# 21_GPIOs_EXP.net
KiCad netlist of a schematic drawn in Altium Designer
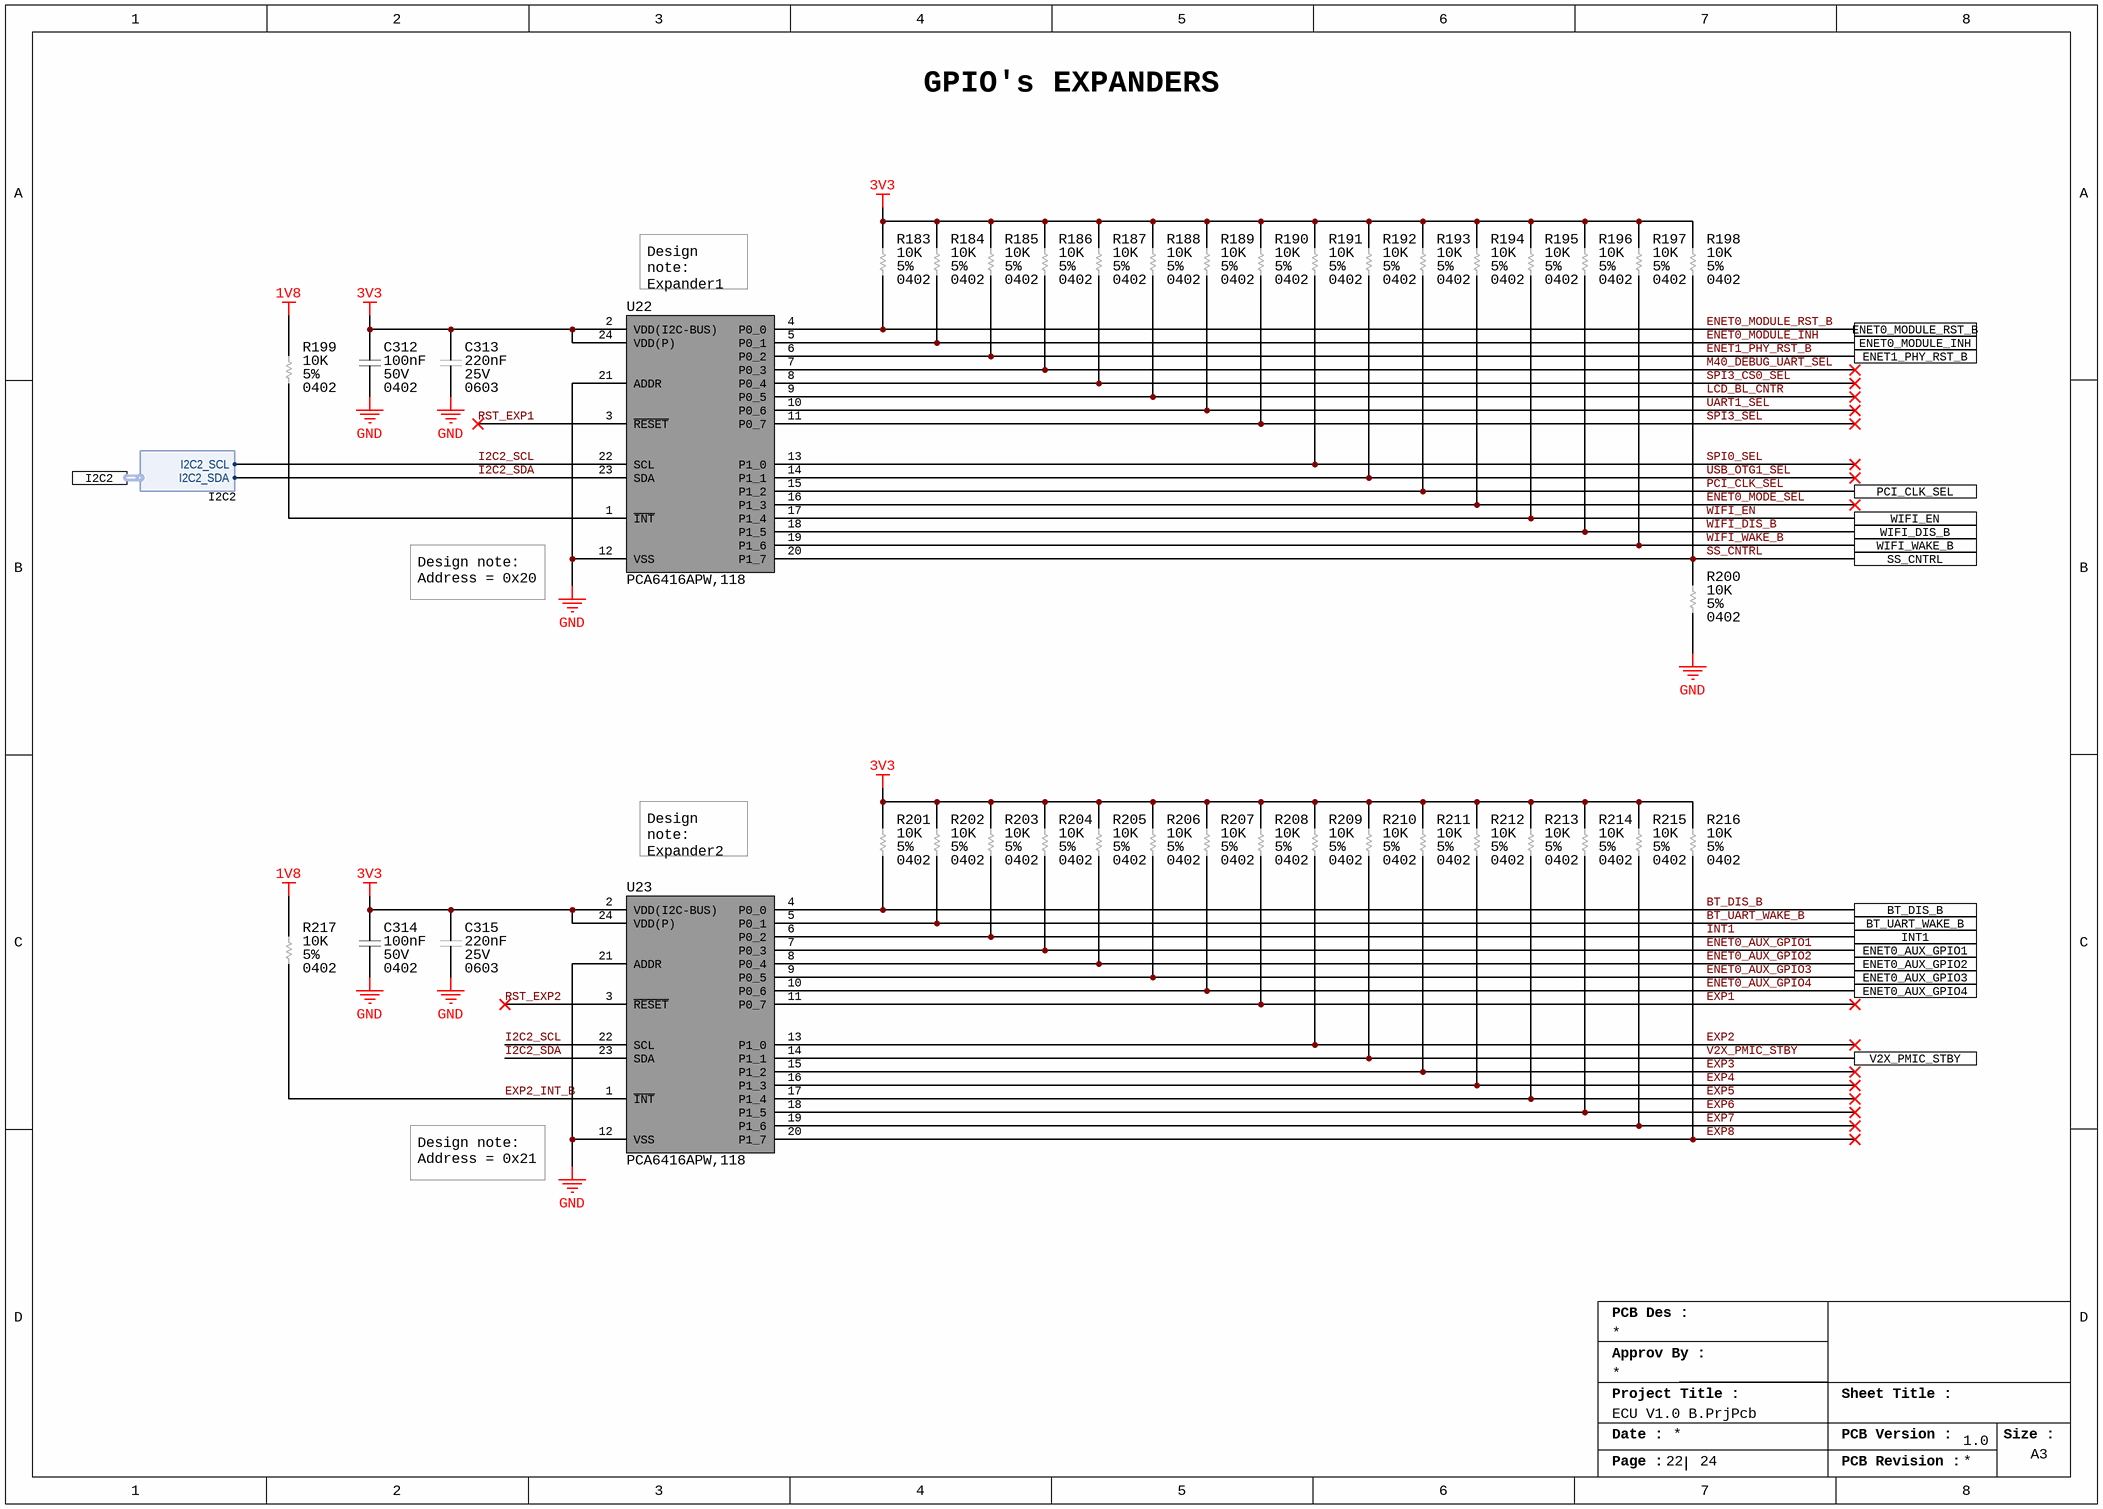
[diagram p0: 21_GPIOs_EXP.SchDoc]

(export (version "E")
  (design (tool "Eeschema 10.0.6"))
  (components
    (comp (ref "C312")
      (value "GRM155R71H104KE14D")
      (footprint "CAP_0402_CAPC1005X05N")
      (description "Multilayer Ceramic Capacitor, 0.1 uF, 16 V, ± 10%, X7R, 0402 [1005 Metric]")
      (fields
        (field (name "MANUFACTURER") "Murata")
        (field (name "TOLERANCE") "10%")
        (field (name "VOLTAGE RATING") "50V")
        (field (name "CAPACITANCE") "100nF")
        (field (name "CASE/PACKAGE") "0402")
      )
      (libsource (lib "Electronic Devices_LIB") (part "CAP_100NF_50V_X7R_0402"))
    )
    (comp (ref "C313")
      (value "GRM188R71E224KA88D")
      (footprint "CAP_0603_CAPC1608X08N")
      (description "Multilayer Ceramic Capacitor, 0.22 uF, 25 V, ± 10%, X7R, 0603 [1608 Metric]")
      (fields
        (field (name "MANUFACTURER") "Murata")
        (field (name "TOLERANCE") "10%")
        (field (name "CASE/PACKAGE") "0603")
        (field (name "VOLTAGE RATING") "25V")
        (field (name "CAPACITANCE") "220nF")
      )
      (libsource (lib "Electronic Devices_LIB") (part "CAP_0.22uF_25V_X7R_0603"))
    )
    (comp (ref "C314")
      (value "GRM155R71H104KE14D")
      (footprint "CAP_0402_CAPC1005X05N")
      (description "Multilayer Ceramic Capacitor, 0.1 uF, 16 V, ± 10%, X7R, 0402 [1005 Metric]")
      (fields
        (field (name "MANUFACTURER") "Murata")
        (field (name "TOLERANCE") "10%")
        (field (name "VOLTAGE RATING") "50V")
        (field (name "CAPACITANCE") "100nF")
        (field (name "CASE/PACKAGE") "0402")
      )
      (libsource (lib "Electronic Devices_LIB") (part "CAP_100NF_50V_X7R_0402"))
    )
    (comp (ref "C315")
      (value "GRM188R71E224KA88D")
      (footprint "CAP_0603_CAPC1608X08N")
      (description "Multilayer Ceramic Capacitor, 0.22 uF, 25 V, ± 10%, X7R, 0603 [1608 Metric]")
      (fields
        (field (name "MANUFACTURER") "Murata")
        (field (name "TOLERANCE") "10%")
        (field (name "CASE/PACKAGE") "0603")
        (field (name "VOLTAGE RATING") "25V")
        (field (name "CAPACITANCE") "220nF")
      )
      (libsource (lib "Electronic Devices_LIB") (part "CAP_0.22uF_25V_X7R_0603"))
    )
    (comp (ref "R183")
      (value "ERJ-2GEJ103X")
      (footprint "RES_0402_RESC1005X04N")
      (description "Res Thick Film 0402 10K Ohm 5% 1/10W ±200ppm/°C Molded SMD Punched Carrier T/R")
      (fields
        (field (name "MANUFACTURER") "Panasonic")
        (field (name "TOLERANCE") "5%")
        (field (name "RESISTANCE") "10K")
        (field (name "CASE/PACKAGE") "0402")
      )
      (libsource (lib "Electronic Devices_LIB") (part "RES_10K_5%_100mW_0402"))
    )
    (comp (ref "R184")
      (value "ERJ-2GEJ103X")
      (footprint "RES_0402_RESC1005X04N")
      (description "Res Thick Film 0402 10K Ohm 5% 1/10W ±200ppm/°C Molded SMD Punched Carrier T/R")
      (fields
        (field (name "MANUFACTURER") "Panasonic")
        (field (name "TOLERANCE") "5%")
        (field (name "RESISTANCE") "10K")
        (field (name "CASE/PACKAGE") "0402")
      )
      (libsource (lib "Electronic Devices_LIB") (part "RES_10K_5%_100mW_0402"))
    )
    (comp (ref "R185")
      (value "ERJ-2GEJ103X")
      (footprint "RES_0402_RESC1005X04N")
      (description "Res Thick Film 0402 10K Ohm 5% 1/10W ±200ppm/°C Molded SMD Punched Carrier T/R")
      (fields
        (field (name "MANUFACTURER") "Panasonic")
        (field (name "TOLERANCE") "5%")
        (field (name "RESISTANCE") "10K")
        (field (name "CASE/PACKAGE") "0402")
      )
      (libsource (lib "Electronic Devices_LIB") (part "RES_10K_5%_100mW_0402"))
    )
    (comp (ref "R186")
      (value "ERJ-2GEJ103X")
      (footprint "RES_0402_RESC1005X04N")
      (description "Res Thick Film 0402 10K Ohm 5% 1/10W ±200ppm/°C Molded SMD Punched Carrier T/R")
      (fields
        (field (name "MANUFACTURER") "Panasonic")
        (field (name "TOLERANCE") "5%")
        (field (name "RESISTANCE") "10K")
        (field (name "CASE/PACKAGE") "0402")
      )
      (libsource (lib "Electronic Devices_LIB") (part "RES_10K_5%_100mW_0402"))
    )
    (comp (ref "R187")
      (value "ERJ-2GEJ103X")
      (footprint "RES_0402_RESC1005X04N")
      (description "Res Thick Film 0402 10K Ohm 5% 1/10W ±200ppm/°C Molded SMD Punched Carrier T/R")
      (fields
        (field (name "MANUFACTURER") "Panasonic")
        (field (name "TOLERANCE") "5%")
        (field (name "RESISTANCE") "10K")
        (field (name "CASE/PACKAGE") "0402")
      )
      (libsource (lib "Electronic Devices_LIB") (part "RES_10K_5%_100mW_0402"))
    )
    (comp (ref "R188")
      (value "ERJ-2GEJ103X")
      (footprint "RES_0402_RESC1005X04N")
      (description "Res Thick Film 0402 10K Ohm 5% 1/10W ±200ppm/°C Molded SMD Punched Carrier T/R")
      (fields
        (field (name "MANUFACTURER") "Panasonic")
        (field (name "TOLERANCE") "5%")
        (field (name "RESISTANCE") "10K")
        (field (name "CASE/PACKAGE") "0402")
      )
      (libsource (lib "Electronic Devices_LIB") (part "RES_10K_5%_100mW_0402"))
    )
    (comp (ref "R189")
      (value "ERJ-2GEJ103X")
      (footprint "RES_0402_RESC1005X04N")
      (description "Res Thick Film 0402 10K Ohm 5% 1/10W ±200ppm/°C Molded SMD Punched Carrier T/R")
      (fields
        (field (name "MANUFACTURER") "Panasonic")
        (field (name "TOLERANCE") "5%")
        (field (name "RESISTANCE") "10K")
        (field (name "CASE/PACKAGE") "0402")
      )
      (libsource (lib "Electronic Devices_LIB") (part "RES_10K_5%_100mW_0402"))
    )
    (comp (ref "R190")
      (value "ERJ-2GEJ103X")
      (footprint "RES_0402_RESC1005X04N")
      (description "Res Thick Film 0402 10K Ohm 5% 1/10W ±200ppm/°C Molded SMD Punched Carrier T/R")
      (fields
        (field (name "MANUFACTURER") "Panasonic")
        (field (name "TOLERANCE") "5%")
        (field (name "RESISTANCE") "10K")
        (field (name "CASE/PACKAGE") "0402")
      )
      (libsource (lib "Electronic Devices_LIB") (part "RES_10K_5%_100mW_0402"))
    )
    (comp (ref "R191")
      (value "ERJ-2GEJ103X")
      (footprint "RES_0402_RESC1005X04N")
      (description "Res Thick Film 0402 10K Ohm 5% 1/10W ±200ppm/°C Molded SMD Punched Carrier T/R")
      (fields
        (field (name "MANUFACTURER") "Panasonic")
        (field (name "TOLERANCE") "5%")
        (field (name "RESISTANCE") "10K")
        (field (name "CASE/PACKAGE") "0402")
      )
      (libsource (lib "Electronic Devices_LIB") (part "RES_10K_5%_100mW_0402"))
    )
    (comp (ref "R192")
      (value "ERJ-2GEJ103X")
      (footprint "RES_0402_RESC1005X04N")
      (description "Res Thick Film 0402 10K Ohm 5% 1/10W ±200ppm/°C Molded SMD Punched Carrier T/R")
      (fields
        (field (name "MANUFACTURER") "Panasonic")
        (field (name "TOLERANCE") "5%")
        (field (name "RESISTANCE") "10K")
        (field (name "CASE/PACKAGE") "0402")
      )
      (libsource (lib "Electronic Devices_LIB") (part "RES_10K_5%_100mW_0402"))
    )
    (comp (ref "R193")
      (value "ERJ-2GEJ103X")
      (footprint "RES_0402_RESC1005X04N")
      (description "Res Thick Film 0402 10K Ohm 5% 1/10W ±200ppm/°C Molded SMD Punched Carrier T/R")
      (fields
        (field (name "MANUFACTURER") "Panasonic")
        (field (name "TOLERANCE") "5%")
        (field (name "RESISTANCE") "10K")
        (field (name "CASE/PACKAGE") "0402")
      )
      (libsource (lib "Electronic Devices_LIB") (part "RES_10K_5%_100mW_0402"))
    )
    (comp (ref "R194")
      (value "ERJ-2GEJ103X")
      (footprint "RES_0402_RESC1005X04N")
      (description "Res Thick Film 0402 10K Ohm 5% 1/10W ±200ppm/°C Molded SMD Punched Carrier T/R")
      (fields
        (field (name "MANUFACTURER") "Panasonic")
        (field (name "TOLERANCE") "5%")
        (field (name "RESISTANCE") "10K")
        (field (name "CASE/PACKAGE") "0402")
      )
      (libsource (lib "Electronic Devices_LIB") (part "RES_10K_5%_100mW_0402"))
    )
    (comp (ref "R195")
      (value "ERJ-2GEJ103X")
      (footprint "RES_0402_RESC1005X04N")
      (description "Res Thick Film 0402 10K Ohm 5% 1/10W ±200ppm/°C Molded SMD Punched Carrier T/R")
      (fields
        (field (name "MANUFACTURER") "Panasonic")
        (field (name "TOLERANCE") "5%")
        (field (name "RESISTANCE") "10K")
        (field (name "CASE/PACKAGE") "0402")
      )
      (libsource (lib "Electronic Devices_LIB") (part "RES_10K_5%_100mW_0402"))
    )
    (comp (ref "R196")
      (value "ERJ-2GEJ103X")
      (footprint "RES_0402_RESC1005X04N")
      (description "Res Thick Film 0402 10K Ohm 5% 1/10W ±200ppm/°C Molded SMD Punched Carrier T/R")
      (fields
        (field (name "MANUFACTURER") "Panasonic")
        (field (name "TOLERANCE") "5%")
        (field (name "RESISTANCE") "10K")
        (field (name "CASE/PACKAGE") "0402")
      )
      (libsource (lib "Electronic Devices_LIB") (part "RES_10K_5%_100mW_0402"))
    )
    (comp (ref "R197")
      (value "ERJ-2GEJ103X")
      (footprint "RES_0402_RESC1005X04N")
      (description "Res Thick Film 0402 10K Ohm 5% 1/10W ±200ppm/°C Molded SMD Punched Carrier T/R")
      (fields
        (field (name "MANUFACTURER") "Panasonic")
        (field (name "TOLERANCE") "5%")
        (field (name "RESISTANCE") "10K")
        (field (name "CASE/PACKAGE") "0402")
      )
      (libsource (lib "Electronic Devices_LIB") (part "RES_10K_5%_100mW_0402"))
    )
    (comp (ref "R198")
      (value "ERJ-2GEJ103X")
      (footprint "RES_0402_RESC1005X04N")
      (description "Res Thick Film 0402 10K Ohm 5% 1/10W ±200ppm/°C Molded SMD Punched Carrier T/R")
      (fields
        (field (name "MANUFACTURER") "Panasonic")
        (field (name "TOLERANCE") "5%")
        (field (name "RESISTANCE") "10K")
        (field (name "CASE/PACKAGE") "0402")
      )
      (libsource (lib "Electronic Devices_LIB") (part "RES_10K_5%_100mW_0402"))
    )
    (comp (ref "R199")
      (value "ERJ-2GEJ103X")
      (footprint "RES_0402_RESC1005X04N")
      (description "Res Thick Film 0402 10K Ohm 5% 1/10W ±200ppm/°C Molded SMD Punched Carrier T/R")
      (fields
        (field (name "MANUFACTURER") "Panasonic")
        (field (name "TOLERANCE") "5%")
        (field (name "RESISTANCE") "10K")
        (field (name "CASE/PACKAGE") "0402")
      )
      (libsource (lib "Electronic Devices_LIB") (part "RES_10K_5%_100mW_0402"))
    )
    (comp (ref "R200")
      (value "ERJ-2GEJ103X")
      (footprint "RES_0402_RESC1005X04N")
      (description "Res Thick Film 0402 10K Ohm 5% 1/10W ±200ppm/°C Molded SMD Punched Carrier T/R")
      (fields
        (field (name "MANUFACTURER") "Panasonic")
        (field (name "TOLERANCE") "5%")
        (field (name "RESISTANCE") "10K")
        (field (name "CASE/PACKAGE") "0402")
      )
      (libsource (lib "Electronic Devices_LIB") (part "RES_10K_5%_100mW_0402"))
    )
    (comp (ref "R201")
      (value "ERJ-2GEJ103X")
      (footprint "RES_0402_RESC1005X04N")
      (description "Res Thick Film 0402 10K Ohm 5% 1/10W ±200ppm/°C Molded SMD Punched Carrier T/R")
      (fields
        (field (name "MANUFACTURER") "Panasonic")
        (field (name "TOLERANCE") "5%")
        (field (name "RESISTANCE") "10K")
        (field (name "CASE/PACKAGE") "0402")
      )
      (libsource (lib "Electronic Devices_LIB") (part "RES_10K_5%_100mW_0402"))
    )
    (comp (ref "R202")
      (value "ERJ-2GEJ103X")
      (footprint "RES_0402_RESC1005X04N")
      (description "Res Thick Film 0402 10K Ohm 5% 1/10W ±200ppm/°C Molded SMD Punched Carrier T/R")
      (fields
        (field (name "MANUFACTURER") "Panasonic")
        (field (name "TOLERANCE") "5%")
        (field (name "RESISTANCE") "10K")
        (field (name "CASE/PACKAGE") "0402")
      )
      (libsource (lib "Electronic Devices_LIB") (part "RES_10K_5%_100mW_0402"))
    )
    (comp (ref "R203")
      (value "ERJ-2GEJ103X")
      (footprint "RES_0402_RESC1005X04N")
      (description "Res Thick Film 0402 10K Ohm 5% 1/10W ±200ppm/°C Molded SMD Punched Carrier T/R")
      (fields
        (field (name "MANUFACTURER") "Panasonic")
        (field (name "TOLERANCE") "5%")
        (field (name "RESISTANCE") "10K")
        (field (name "CASE/PACKAGE") "0402")
      )
      (libsource (lib "Electronic Devices_LIB") (part "RES_10K_5%_100mW_0402"))
    )
    (comp (ref "R204")
      (value "ERJ-2GEJ103X")
      (footprint "RES_0402_RESC1005X04N")
      (description "Res Thick Film 0402 10K Ohm 5% 1/10W ±200ppm/°C Molded SMD Punched Carrier T/R")
      (fields
        (field (name "MANUFACTURER") "Panasonic")
        (field (name "TOLERANCE") "5%")
        (field (name "RESISTANCE") "10K")
        (field (name "CASE/PACKAGE") "0402")
      )
      (libsource (lib "Electronic Devices_LIB") (part "RES_10K_5%_100mW_0402"))
    )
    (comp (ref "R205")
      (value "ERJ-2GEJ103X")
      (footprint "RES_0402_RESC1005X04N")
      (description "Res Thick Film 0402 10K Ohm 5% 1/10W ±200ppm/°C Molded SMD Punched Carrier T/R")
      (fields
        (field (name "MANUFACTURER") "Panasonic")
        (field (name "TOLERANCE") "5%")
        (field (name "RESISTANCE") "10K")
        (field (name "CASE/PACKAGE") "0402")
      )
      (libsource (lib "Electronic Devices_LIB") (part "RES_10K_5%_100mW_0402"))
    )
    (comp (ref "R206")
      (value "ERJ-2GEJ103X")
      (footprint "RES_0402_RESC1005X04N")
      (description "Res Thick Film 0402 10K Ohm 5% 1/10W ±200ppm/°C Molded SMD Punched Carrier T/R")
      (fields
        (field (name "MANUFACTURER") "Panasonic")
        (field (name "TOLERANCE") "5%")
        (field (name "RESISTANCE") "10K")
        (field (name "CASE/PACKAGE") "0402")
      )
      (libsource (lib "Electronic Devices_LIB") (part "RES_10K_5%_100mW_0402"))
    )
    (comp (ref "R207")
      (value "ERJ-2GEJ103X")
      (footprint "RES_0402_RESC1005X04N")
      (description "Res Thick Film 0402 10K Ohm 5% 1/10W ±200ppm/°C Molded SMD Punched Carrier T/R")
      (fields
        (field (name "MANUFACTURER") "Panasonic")
        (field (name "TOLERANCE") "5%")
        (field (name "RESISTANCE") "10K")
        (field (name "CASE/PACKAGE") "0402")
      )
      (libsource (lib "Electronic Devices_LIB") (part "RES_10K_5%_100mW_0402"))
    )
    (comp (ref "R208")
      (value "ERJ-2GEJ103X")
      (footprint "RES_0402_RESC1005X04N")
      (description "Res Thick Film 0402 10K Ohm 5% 1/10W ±200ppm/°C Molded SMD Punched Carrier T/R")
      (fields
        (field (name "MANUFACTURER") "Panasonic")
        (field (name "TOLERANCE") "5%")
        (field (name "RESISTANCE") "10K")
        (field (name "CASE/PACKAGE") "0402")
      )
      (libsource (lib "Electronic Devices_LIB") (part "RES_10K_5%_100mW_0402"))
    )
    (comp (ref "R209")
      (value "ERJ-2GEJ103X")
      (footprint "RES_0402_RESC1005X04N")
      (description "Res Thick Film 0402 10K Ohm 5% 1/10W ±200ppm/°C Molded SMD Punched Carrier T/R")
      (fields
        (field (name "MANUFACTURER") "Panasonic")
        (field (name "TOLERANCE") "5%")
        (field (name "RESISTANCE") "10K")
        (field (name "CASE/PACKAGE") "0402")
      )
      (libsource (lib "Electronic Devices_LIB") (part "RES_10K_5%_100mW_0402"))
    )
    (comp (ref "R210")
      (value "ERJ-2GEJ103X")
      (footprint "RES_0402_RESC1005X04N")
      (description "Res Thick Film 0402 10K Ohm 5% 1/10W ±200ppm/°C Molded SMD Punched Carrier T/R")
      (fields
        (field (name "MANUFACTURER") "Panasonic")
        (field (name "TOLERANCE") "5%")
        (field (name "RESISTANCE") "10K")
        (field (name "CASE/PACKAGE") "0402")
      )
      (libsource (lib "Electronic Devices_LIB") (part "RES_10K_5%_100mW_0402"))
    )
    (comp (ref "R211")
      (value "ERJ-2GEJ103X")
      (footprint "RES_0402_RESC1005X04N")
      (description "Res Thick Film 0402 10K Ohm 5% 1/10W ±200ppm/°C Molded SMD Punched Carrier T/R")
      (fields
        (field (name "MANUFACTURER") "Panasonic")
        (field (name "TOLERANCE") "5%")
        (field (name "RESISTANCE") "10K")
        (field (name "CASE/PACKAGE") "0402")
      )
      (libsource (lib "Electronic Devices_LIB") (part "RES_10K_5%_100mW_0402"))
    )
    (comp (ref "R212")
      (value "ERJ-2GEJ103X")
      (footprint "RES_0402_RESC1005X04N")
      (description "Res Thick Film 0402 10K Ohm 5% 1/10W ±200ppm/°C Molded SMD Punched Carrier T/R")
      (fields
        (field (name "MANUFACTURER") "Panasonic")
        (field (name "TOLERANCE") "5%")
        (field (name "RESISTANCE") "10K")
        (field (name "CASE/PACKAGE") "0402")
      )
      (libsource (lib "Electronic Devices_LIB") (part "RES_10K_5%_100mW_0402"))
    )
    (comp (ref "R213")
      (value "ERJ-2GEJ103X")
      (footprint "RES_0402_RESC1005X04N")
      (description "Res Thick Film 0402 10K Ohm 5% 1/10W ±200ppm/°C Molded SMD Punched Carrier T/R")
      (fields
        (field (name "MANUFACTURER") "Panasonic")
        (field (name "TOLERANCE") "5%")
        (field (name "RESISTANCE") "10K")
        (field (name "CASE/PACKAGE") "0402")
      )
      (libsource (lib "Electronic Devices_LIB") (part "RES_10K_5%_100mW_0402"))
    )
    (comp (ref "R214")
      (value "ERJ-2GEJ103X")
      (footprint "RES_0402_RESC1005X04N")
      (description "Res Thick Film 0402 10K Ohm 5% 1/10W ±200ppm/°C Molded SMD Punched Carrier T/R")
      (fields
        (field (name "MANUFACTURER") "Panasonic")
        (field (name "TOLERANCE") "5%")
        (field (name "RESISTANCE") "10K")
        (field (name "CASE/PACKAGE") "0402")
      )
      (libsource (lib "Electronic Devices_LIB") (part "RES_10K_5%_100mW_0402"))
    )
    (comp (ref "R215")
      (value "ERJ-2GEJ103X")
      (footprint "RES_0402_RESC1005X04N")
      (description "Res Thick Film 0402 10K Ohm 5% 1/10W ±200ppm/°C Molded SMD Punched Carrier T/R")
      (fields
        (field (name "MANUFACTURER") "Panasonic")
        (field (name "TOLERANCE") "5%")
        (field (name "RESISTANCE") "10K")
        (field (name "CASE/PACKAGE") "0402")
      )
      (libsource (lib "Electronic Devices_LIB") (part "RES_10K_5%_100mW_0402"))
    )
    (comp (ref "R216")
      (value "ERJ-2GEJ103X")
      (footprint "RES_0402_RESC1005X04N")
      (description "Res Thick Film 0402 10K Ohm 5% 1/10W ±200ppm/°C Molded SMD Punched Carrier T/R")
      (fields
        (field (name "MANUFACTURER") "Panasonic")
        (field (name "TOLERANCE") "5%")
        (field (name "RESISTANCE") "10K")
        (field (name "CASE/PACKAGE") "0402")
      )
      (libsource (lib "Electronic Devices_LIB") (part "RES_10K_5%_100mW_0402"))
    )
    (comp (ref "R217")
      (value "ERJ-2GEJ103X")
      (footprint "RES_0402_RESC1005X04N")
      (description "Res Thick Film 0402 10K Ohm 5% 1/10W ±200ppm/°C Molded SMD Punched Carrier T/R")
      (fields
        (field (name "MANUFACTURER") "Panasonic")
        (field (name "TOLERANCE") "5%")
        (field (name "RESISTANCE") "10K")
        (field (name "CASE/PACKAGE") "0402")
      )
      (libsource (lib "Electronic Devices_LIB") (part "RES_10K_5%_100mW_0402"))
    )
    (comp (ref "U22")
      (value "PCA6416APW,118")
      (footprint "PCA6416APW118")
      (description "I2C/SMBus Interface 100kHz/400kHz 5.5V 24-Pin TSSOP T/R")
      (fields (field (name "MANUFACTURER") "NXP Semiconductors"))
      (libsource (lib "Electronic Devices_LIB") (part "IC_EXPANDER_16_PCA6416APW,118"))
    )
    (comp (ref "U23")
      (value "PCA6416APW,118")
      (footprint "PCA6416APW118")
      (description "I2C/SMBus Interface 100kHz/400kHz 5.5V 24-Pin TSSOP T/R")
      (fields (field (name "MANUFACTURER") "NXP Semiconductors"))
      (libsource (lib "Electronic Devices_LIB") (part "IC_EXPANDER_16_PCA6416APW,118"))
    )
  )
  (nets
    (net (code "2") (name "/BT_DIS_B") (class "Default")
      (node (ref "R201") (pin "1") (pinfunction "1_1") (pintype "passive"))
      (node (ref "U23") (pin "4") (pinfunction "P0_0_4") (pintype "passive"))
    )
    (net (code "3") (name "/BT_UART_WAKE_B") (class "Default")
      (node (ref "R202") (pin "1") (pinfunction "1_1") (pintype "passive"))
      (node (ref "U23") (pin "5") (pinfunction "P0_1_5") (pintype "passive"))
    )
    (net (code "4") (name "/ENET0_AUX_GPIO1") (class "Default")
      (node (ref "R204") (pin "1") (pinfunction "1_1") (pintype "passive"))
      (node (ref "U23") (pin "7") (pinfunction "P0_3_7") (pintype "passive"))
    )
    (net (code "5") (name "/ENET0_AUX_GPIO2") (class "Default")
      (node (ref "R205") (pin "1") (pinfunction "1_1") (pintype "passive"))
      (node (ref "U23") (pin "8") (pinfunction "P0_4_8") (pintype "passive"))
    )
    (net (code "6") (name "/ENET0_AUX_GPIO3") (class "Default")
      (node (ref "R206") (pin "1") (pinfunction "1_1") (pintype "passive"))
      (node (ref "U23") (pin "9") (pinfunction "P0_5_9") (pintype "passive"))
    )
    (net (code "7") (name "/ENET0_AUX_GPIO4") (class "Default")
      (node (ref "R207") (pin "1") (pinfunction "1_1") (pintype "passive"))
      (node (ref "U23") (pin "10") (pinfunction "P0_6_10") (pintype "passive"))
    )
    (net (code "8") (name "/ENET0_MODE_SEL") (class "Default")
      (node (ref "R194") (pin "1") (pinfunction "1_1") (pintype "passive"))
      (node (ref "U22") (pin "16") (pinfunction "P1_3_16") (pintype "passive"))
    )
    (net (code "9") (name "/ENET0_MODULE_INH") (class "Default")
      (node (ref "R184") (pin "1") (pinfunction "1_1") (pintype "passive"))
      (node (ref "U22") (pin "5") (pinfunction "P0_1_5") (pintype "passive"))
    )
    (net (code "10") (name "/ENET0_MODULE_RST_B") (class "Default")
      (node (ref "R183") (pin "1") (pinfunction "1_1") (pintype "passive"))
      (node (ref "U22") (pin "4") (pinfunction "P0_0_4") (pintype "passive"))
    )
    (net (code "11") (name "/ENET1_PHY_RST_B") (class "Default")
      (node (ref "R185") (pin "1") (pinfunction "1_1") (pintype "passive"))
      (node (ref "U22") (pin "6") (pinfunction "P0_2_6") (pintype "passive"))
    )
    (net (code "12") (name "/EXP1") (class "Default")
      (node (ref "R208") (pin "1") (pinfunction "1_1") (pintype "passive"))
      (node (ref "U23") (pin "11") (pinfunction "P0_7_11") (pintype "passive"))
    )
    (net (code "13") (name "/EXP2") (class "Default")
      (node (ref "R209") (pin "1") (pinfunction "1_1") (pintype "passive"))
      (node (ref "U23") (pin "13") (pinfunction "P1_0_13") (pintype "passive"))
    )
    (net (code "14") (name "/EXP2_INT_B") (class "Default")
      (node (ref "R217") (pin "1") (pinfunction "1_1") (pintype "passive"))
      (node (ref "U23") (pin "1") (pinfunction "~{INT}_1") (pintype "passive"))
    )
    (net (code "15") (name "/EXP3") (class "Default")
      (node (ref "R211") (pin "1") (pinfunction "1_1") (pintype "passive"))
      (node (ref "U23") (pin "15") (pinfunction "P1_2_15") (pintype "passive"))
    )
    (net (code "16") (name "/EXP4") (class "Default")
      (node (ref "R212") (pin "1") (pinfunction "1_1") (pintype "passive"))
      (node (ref "U23") (pin "16") (pinfunction "P1_3_16") (pintype "passive"))
    )
    (net (code "17") (name "/EXP5") (class "Default")
      (node (ref "R213") (pin "1") (pinfunction "1_1") (pintype "passive"))
      (node (ref "U23") (pin "17") (pinfunction "P1_4_17") (pintype "passive"))
    )
    (net (code "18") (name "/EXP6") (class "Default")
      (node (ref "R214") (pin "1") (pinfunction "1_1") (pintype "passive"))
      (node (ref "U23") (pin "18") (pinfunction "P1_5_18") (pintype "passive"))
    )
    (net (code "19") (name "/EXP7") (class "Default")
      (node (ref "R215") (pin "1") (pinfunction "1_1") (pintype "passive"))
      (node (ref "U23") (pin "19") (pinfunction "P1_6_19") (pintype "passive"))
    )
    (net (code "20") (name "/EXP8") (class "Default")
      (node (ref "R216") (pin "1") (pinfunction "1_1") (pintype "passive"))
      (node (ref "U23") (pin "20") (pinfunction "P1_7_20") (pintype "passive"))
    )
    (net (code "21") (name "/I2C2_SCL") (class "Default")
      (node (ref "U22") (pin "22") (pinfunction "SCL_22") (pintype "passive"))
      (node (ref "U23") (pin "22") (pinfunction "SCL_22") (pintype "passive"))
    )
    (net (code "22") (name "/I2C2_SDA") (class "Default")
      (node (ref "U22") (pin "23") (pinfunction "SDA_23") (pintype "passive"))
      (node (ref "U23") (pin "23") (pinfunction "SDA_23") (pintype "passive"))
    )
    (net (code "23") (name "/INT1") (class "Default")
      (node (ref "R203") (pin "1") (pinfunction "1_1") (pintype "passive"))
      (node (ref "U23") (pin "6") (pinfunction "P0_2_6") (pintype "passive"))
    )
    (net (code "24") (name "/LCD_BL_CNTR") (class "Default")
      (node (ref "R188") (pin "1") (pinfunction "1_1") (pintype "passive"))
      (node (ref "U22") (pin "9") (pinfunction "P0_5_9") (pintype "passive"))
    )
    (net (code "25") (name "/M40_DEBUG_UART_SEL") (class "Default")
      (node (ref "R186") (pin "1") (pinfunction "1_1") (pintype "passive"))
      (node (ref "U22") (pin "7") (pinfunction "P0_3_7") (pintype "passive"))
    )
    (net (code "26") (name "/PCI_CLK_SEL") (class "Default")
      (node (ref "R193") (pin "1") (pinfunction "1_1") (pintype "passive"))
      (node (ref "U22") (pin "15") (pinfunction "P1_2_15") (pintype "passive"))
    )
    (net (code "27") (name "/RST_EXP1") (class "Default")
      (node (ref "U22") (pin "3") (pinfunction "~{RESET}_3") (pintype "passive+no_connect"))
    )
    (net (code "28") (name "/RST_EXP2") (class "Default")
      (node (ref "U23") (pin "3") (pinfunction "~{RESET}_3") (pintype "passive+no_connect"))
    )
    (net (code "29") (name "/SPI0_SEL") (class "Default")
      (node (ref "R191") (pin "1") (pinfunction "1_1") (pintype "passive"))
      (node (ref "U22") (pin "13") (pinfunction "P1_0_13") (pintype "passive"))
    )
    (net (code "30") (name "/SPI3_CS0_SEL") (class "Default")
      (node (ref "R187") (pin "1") (pinfunction "1_1") (pintype "passive"))
      (node (ref "U22") (pin "8") (pinfunction "P0_4_8") (pintype "passive"))
    )
    (net (code "31") (name "/SPI3_SEL") (class "Default")
      (node (ref "R190") (pin "1") (pinfunction "1_1") (pintype "passive"))
      (node (ref "U22") (pin "11") (pinfunction "P0_7_11") (pintype "passive"))
    )
    (net (code "32") (name "/SS_CNTRL") (class "Default")
      (node (ref "R198") (pin "1") (pinfunction "1_1") (pintype "passive"))
      (node (ref "R200") (pin "2") (pinfunction "2_2") (pintype "passive"))
      (node (ref "U22") (pin "20") (pinfunction "P1_7_20") (pintype "passive"))
    )
    (net (code "33") (name "/UART1_SEL") (class "Default")
      (node (ref "R189") (pin "1") (pinfunction "1_1") (pintype "passive"))
      (node (ref "U22") (pin "10") (pinfunction "P0_6_10") (pintype "passive"))
    )
    (net (code "34") (name "/USB_OTG1_SEL") (class "Default")
      (node (ref "R192") (pin "1") (pinfunction "1_1") (pintype "passive"))
      (node (ref "U22") (pin "14") (pinfunction "P1_1_14") (pintype "passive"))
    )
    (net (code "35") (name "/V2X_PMIC_STBY") (class "Default")
      (node (ref "R210") (pin "1") (pinfunction "1_1") (pintype "passive"))
      (node (ref "U23") (pin "14") (pinfunction "P1_1_14") (pintype "passive"))
    )
    (net (code "36") (name "/WIFI_DIS_B") (class "Default")
      (node (ref "R196") (pin "1") (pinfunction "1_1") (pintype "passive"))
      (node (ref "U22") (pin "18") (pinfunction "P1_5_18") (pintype "passive"))
    )
    (net (code "37") (name "/WIFI_EN") (class "Default")
      (node (ref "R195") (pin "1") (pinfunction "1_1") (pintype "passive"))
      (node (ref "U22") (pin "17") (pinfunction "P1_4_17") (pintype "passive"))
    )
    (net (code "38") (name "/WIFI_WAKE_B") (class "Default")
      (node (ref "R197") (pin "1") (pinfunction "1_1") (pintype "passive"))
      (node (ref "U22") (pin "19") (pinfunction "P1_6_19") (pintype "passive"))
    )
    (net (code "40") (name "1V8") (class "Default")
      (node (ref "R199") (pin "2") (pinfunction "2_2") (pintype "passive"))
      (node (ref "R217") (pin "2") (pinfunction "2_2") (pintype "passive"))
    )
    (net (code "41") (name "3V3") (class "Default")
      (node (ref "C312") (pin "2") (pinfunction "2_2") (pintype "passive"))
      (node (ref "C313") (pin "2") (pinfunction "2_2") (pintype "passive"))
      (node (ref "C314") (pin "2") (pinfunction "2_2") (pintype "passive"))
      (node (ref "C315") (pin "2") (pinfunction "2_2") (pintype "passive"))
      (node (ref "R183") (pin "2") (pinfunction "2_2") (pintype "passive"))
      (node (ref "R184") (pin "2") (pinfunction "2_2") (pintype "passive"))
      (node (ref "R185") (pin "2") (pinfunction "2_2") (pintype "passive"))
      (node (ref "R186") (pin "2") (pinfunction "2_2") (pintype "passive"))
      (node (ref "R187") (pin "2") (pinfunction "2_2") (pintype "passive"))
      (node (ref "R188") (pin "2") (pinfunction "2_2") (pintype "passive"))
      (node (ref "R189") (pin "2") (pinfunction "2_2") (pintype "passive"))
      (node (ref "R190") (pin "2") (pinfunction "2_2") (pintype "passive"))
      (node (ref "R191") (pin "2") (pinfunction "2_2") (pintype "passive"))
      (node (ref "R192") (pin "2") (pinfunction "2_2") (pintype "passive"))
      (node (ref "R193") (pin "2") (pinfunction "2_2") (pintype "passive"))
      (node (ref "R194") (pin "2") (pinfunction "2_2") (pintype "passive"))
      (node (ref "R195") (pin "2") (pinfunction "2_2") (pintype "passive"))
      (node (ref "R196") (pin "2") (pinfunction "2_2") (pintype "passive"))
      (node (ref "R197") (pin "2") (pinfunction "2_2") (pintype "passive"))
      (node (ref "R198") (pin "2") (pinfunction "2_2") (pintype "passive"))
      (node (ref "R201") (pin "2") (pinfunction "2_2") (pintype "passive"))
      (node (ref "R202") (pin "2") (pinfunction "2_2") (pintype "passive"))
      (node (ref "R203") (pin "2") (pinfunction "2_2") (pintype "passive"))
      (node (ref "R204") (pin "2") (pinfunction "2_2") (pintype "passive"))
      (node (ref "R205") (pin "2") (pinfunction "2_2") (pintype "passive"))
      (node (ref "R206") (pin "2") (pinfunction "2_2") (pintype "passive"))
      (node (ref "R207") (pin "2") (pinfunction "2_2") (pintype "passive"))
      (node (ref "R208") (pin "2") (pinfunction "2_2") (pintype "passive"))
      (node (ref "R209") (pin "2") (pinfunction "2_2") (pintype "passive"))
      (node (ref "R210") (pin "2") (pinfunction "2_2") (pintype "passive"))
      (node (ref "R211") (pin "2") (pinfunction "2_2") (pintype "passive"))
      (node (ref "R212") (pin "2") (pinfunction "2_2") (pintype "passive"))
      (node (ref "R213") (pin "2") (pinfunction "2_2") (pintype "passive"))
      (node (ref "R214") (pin "2") (pinfunction "2_2") (pintype "passive"))
      (node (ref "R215") (pin "2") (pinfunction "2_2") (pintype "passive"))
      (node (ref "R216") (pin "2") (pinfunction "2_2") (pintype "passive"))
      (node (ref "U22") (pin "2") (pinfunction "VDD(I2C-BUS)_2") (pintype "passive"))
      (node (ref "U22") (pin "24") (pinfunction "VDD(P)_24") (pintype "passive"))
      (node (ref "U23") (pin "2") (pinfunction "VDD(I2C-BUS)_2") (pintype "passive"))
      (node (ref "U23") (pin "24") (pinfunction "VDD(P)_24") (pintype "passive"))
    )
    (net (code "42") (name "GND") (class "Default")
      (node (ref "C312") (pin "1") (pinfunction "1_1") (pintype "passive"))
      (node (ref "C313") (pin "1") (pinfunction "1_1") (pintype "passive"))
      (node (ref "C314") (pin "1") (pinfunction "1_1") (pintype "passive"))
      (node (ref "C315") (pin "1") (pinfunction "1_1") (pintype "passive"))
      (node (ref "R200") (pin "1") (pinfunction "1_1") (pintype "passive"))
      (node (ref "U22") (pin "12") (pinfunction "VSS_12") (pintype "passive"))
      (node (ref "U22") (pin "21") (pinfunction "ADDR_21") (pintype "passive"))
      (node (ref "U23") (pin "12") (pinfunction "VSS_12") (pintype "passive"))
      (node (ref "U23") (pin "21") (pinfunction "ADDR_21") (pintype "passive"))
    )
    (net (code "43") (name "Net-(U22-~{INT})") (class "Default")
      (node (ref "R199") (pin "1") (pinfunction "1_1") (pintype "passive"))
      (node (ref "U22") (pin "1") (pinfunction "~{INT}_1") (pintype "passive"))
    )
  )
)
